# ltc4063-test.net
KiCad netlist of a schematic drawn in EAGLE
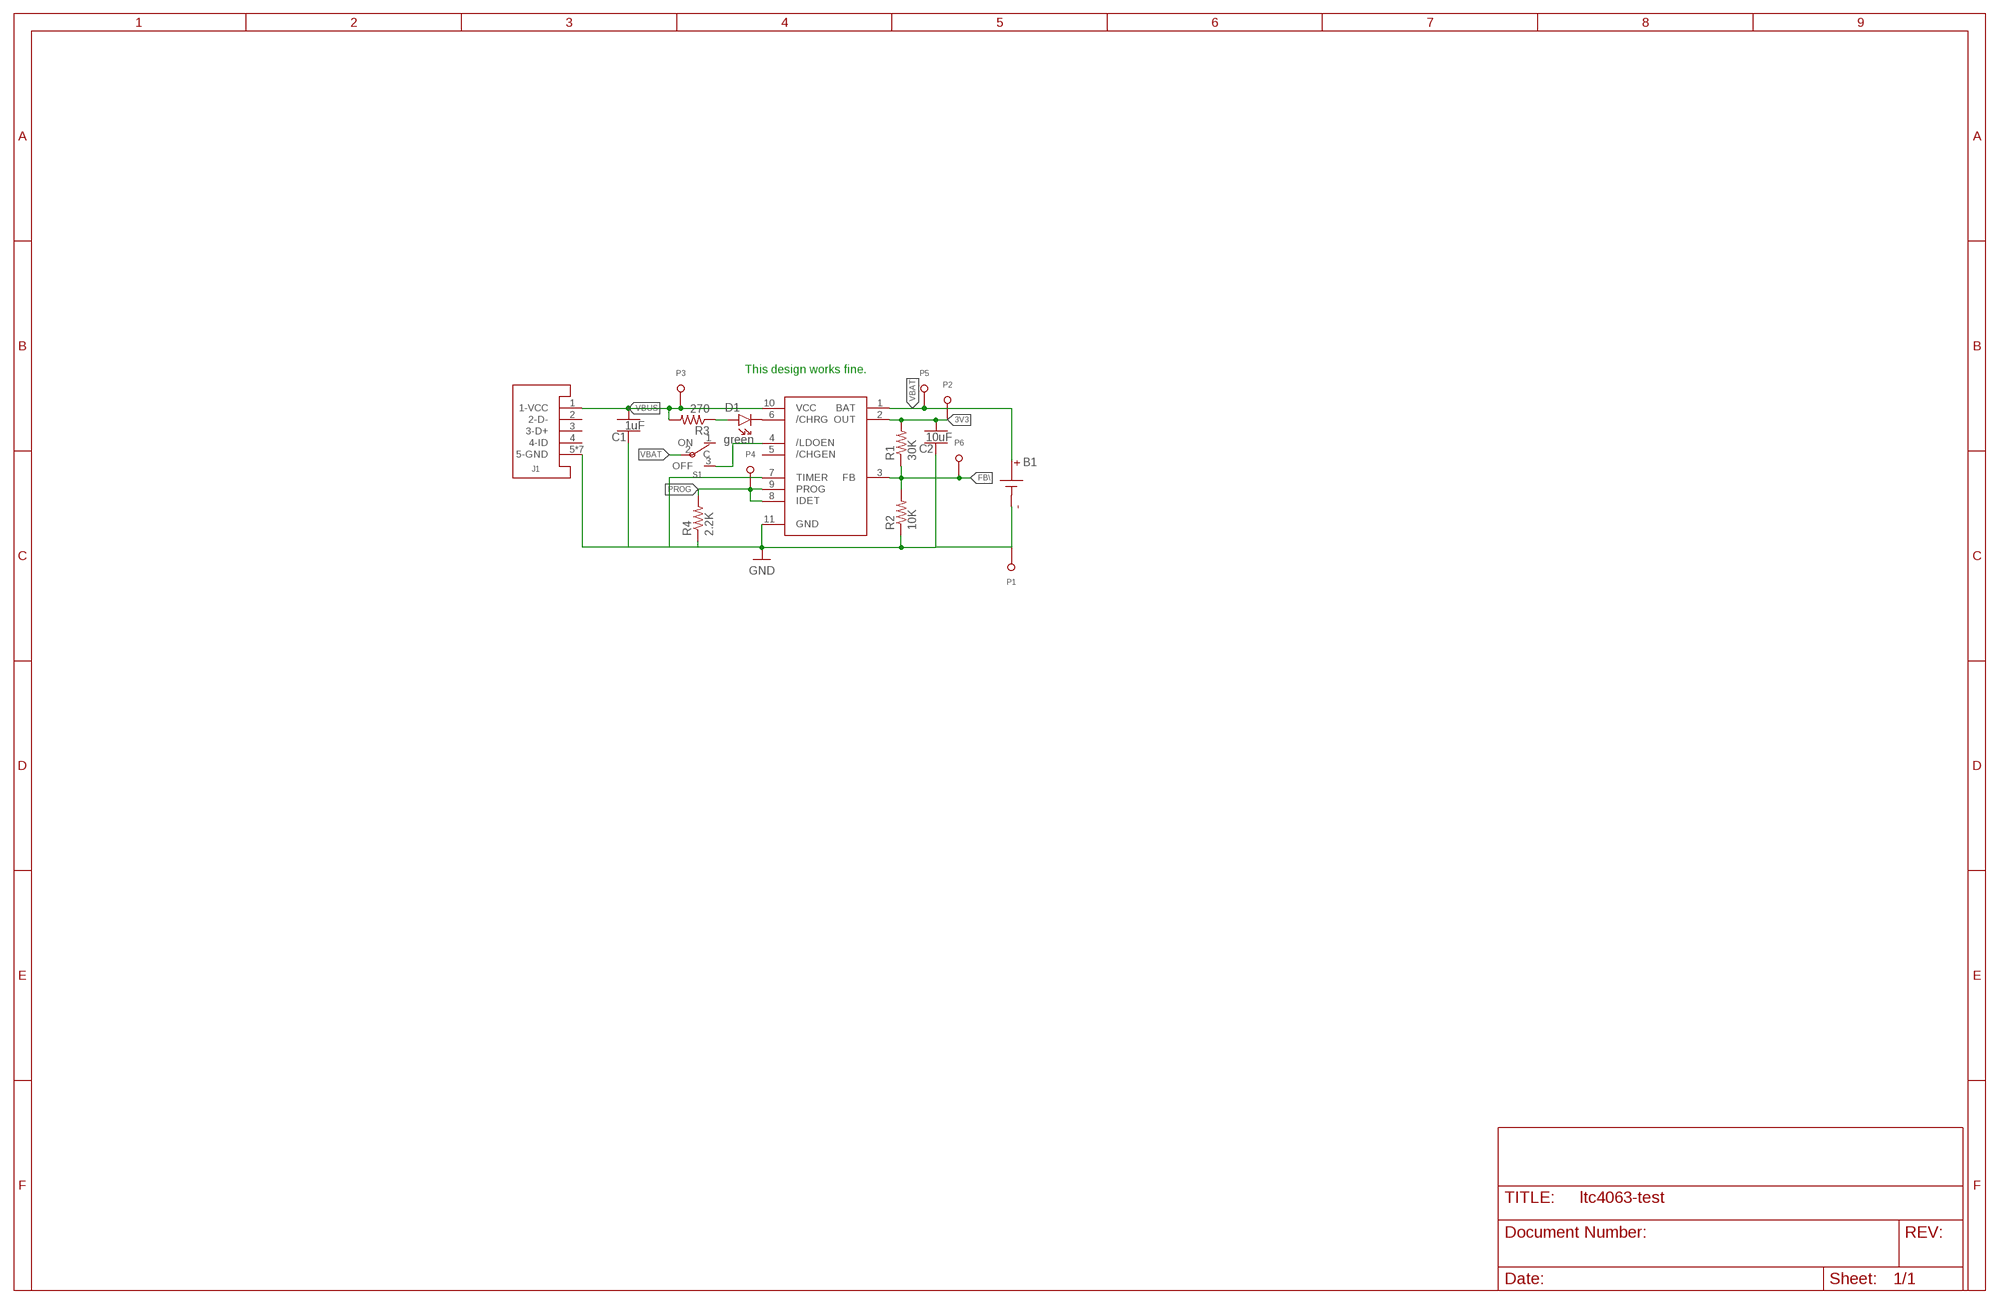
[diagram p0: schematic, sheet 1]

(export (version "E")
  (design (tool "Eeschema 10.0.6"))
  (components
    (comp (ref "B1")
      (value "BATTERY-SPRING-SMD")
      (footprint "eagle-import:WIRE-TERMINAL-1X2-2.5MM-SMD-AVX-009276002021106")
      (fields (field (name "CREATOR") "Swanson"))
      (libsource (lib "eagle-import") (part "BATTERY-SPRING-SMD"))
    )
    (comp (ref "C1")
      (value "1uF")
      (footprint "eagle-import:CAPC2012X140_HS")
      (fields
        (field (name "MFR") "Taiyo Yuden")
        (field (name "MPN") "TMK212B7105KG-T")
        (field (name "CREATOR") "Swanson")
        (field (name "REVIEWER") "Swanson")
      )
      (libsource (lib "eagle-import") (part "CAPACITOR-NP_SMD-2012-0805_CERAMIC-1UF"))
    )
    (comp (ref "C2")
      (value "10uF")
      (footprint "eagle-import:CAPC2012X140_HS")
      (fields (field (name "CREATOR") "Swanson") (field (name "REVIEWER") "Swanson"))
      (libsource (lib "eagle-import") (part "CAPACITOR-NP_SMD-2012-0805_CERAMIC-10UF"))
    )
    (comp (ref "D1")
      (value "green")
      (footprint "eagle-import:LEDSC125X200X120-2_HS")
      (fields
        (field (name "MFR") "Lite-On Inc")
        (field (name "MPN") "LTST-C170GKT")
        (field (name "CREATOR") "Swanson")
        (field (name "REVIEWER") "Swanson")
      )
      (libsource (lib "eagle-import") (part "DIODE-LED_SMD-2012-0805-GREEN"))
    )
    (comp (ref "J1")
      (value "USB-MICROA-AMPHENOL-10118192-0001LF")
      (footprint "eagle-import:USB-MICROA-10118192-0001LF")
      (fields (field (name "CREATOR") "Swanson"))
      (libsource (lib "eagle-import") (part "USB-MICROA-AMPHENOL-10118192-0001LF"))
    )
    (comp (ref "P1")
      (value "TEST-POINT")
      (footprint "eagle-import:TEST-POINT-KEYSTONE-5000")
      (fields (field (name "CREATOR") "Swanson"))
      (libsource (lib "eagle-import") (part "TEST-POINT"))
    )
    (comp (ref "P2")
      (value "TEST-POINT")
      (footprint "eagle-import:TEST-POINT-KEYSTONE-5000")
      (fields (field (name "CREATOR") "Swanson"))
      (libsource (lib "eagle-import") (part "TEST-POINT"))
    )
    (comp (ref "P3")
      (value "TEST-POINT")
      (footprint "eagle-import:TEST-POINT-KEYSTONE-5000")
      (fields (field (name "CREATOR") "Swanson"))
      (libsource (lib "eagle-import") (part "TEST-POINT"))
    )
    (comp (ref "P4")
      (value "TEST-POINT")
      (footprint "eagle-import:TEST-POINT-KEYSTONE-5000")
      (fields (field (name "CREATOR") "Swanson"))
      (libsource (lib "eagle-import") (part "TEST-POINT"))
    )
    (comp (ref "P5")
      (value "TEST-POINT")
      (footprint "eagle-import:TEST-POINT-KEYSTONE-5000")
      (fields (field (name "CREATOR") "Swanson"))
      (libsource (lib "eagle-import") (part "TEST-POINT"))
    )
    (comp (ref "P6")
      (value "TEST-POINT")
      (footprint "eagle-import:TEST-POINT-KEYSTONE-5000")
      (fields (field (name "CREATOR") "Swanson"))
      (libsource (lib "eagle-import") (part "TEST-POINT"))
    )
    (comp (ref "R1")
      (value "30K")
      (footprint "eagle-import:RESC2012X60_HS")
      (fields (field (name "CREATOR") "Swanson"))
      (libsource (lib "eagle-import") (part "RESISTOR_SMD-2012-0805-30K"))
    )
    (comp (ref "R2")
      (value "10K")
      (footprint "eagle-import:RESC2012X60_HS")
      (fields
        (field (name "MFR") "Yageo")
        (field (name "MPN") "RC0805JR-0710KL")
        (field (name "CREATOR") "Swanson")
        (field (name "REVIEWER") "Swanson")
      )
      (libsource (lib "eagle-import") (part "RESISTOR_SMD-2012-0805-10K"))
    )
    (comp (ref "R3")
      (value "270")
      (footprint "eagle-import:RESC2012X60_HS")
      (fields (field (name "CREATOR") "SWANSON"))
      (libsource (lib "eagle-import") (part "RESISTOR_SMD-2012-0805-270"))
    )
    (comp (ref "R4")
      (value "2.2K")
      (footprint "eagle-import:RESC2012X60_HS")
      (fields (field (name "CREATOR") "SWANSON"))
      (libsource (lib "eagle-import") (part "RESISTOR_SMD-2012-0805-2.2K"))
    )
    (comp (ref "S1")
      (value "POWER-SWITCH-MFS201N-9-Z-SMD-VERTICAL")
      (footprint "eagle-import:JS102011JCQN")
      (fields (field (name "CREATOR") "Swanson"))
      (libsource (lib "eagle-import") (part "POWER-SWITCH-MFS201N-9-Z-SMD-VERTICAL"))
    )
    (comp (ref "U1")
      (value "LIPO-VREG-LTC4063")
      (footprint "eagle-import:SON50P300X300X80-11T165X238")
      (fields (field (name "CREATOR") "Swanson"))
      (libsource (lib "eagle-import") (part "LIPO-VREG-LTC4063"))
    )
  )
  (nets
    (net (code "1") (name "3V3") (class "Default")
      (node (ref "C2") (pin "2") (pinfunction "2_2") (pintype "passive"))
      (node (ref "P2") (pin "T") (pinfunction "T_T") (pintype "bidirectional"))
      (node (ref "R1") (pin "2") (pinfunction "2_2") (pintype "passive"))
      (node (ref "U1") (pin "2") (pinfunction "OUT_2") (pintype "bidirectional"))
    )
    (net (code "2") (name "FB\\") (class "Default")
      (node (ref "P6") (pin "T") (pinfunction "T_T") (pintype "bidirectional"))
      (node (ref "R1") (pin "1") (pinfunction "1_1") (pintype "passive"))
      (node (ref "R2") (pin "2") (pinfunction "2_2") (pintype "passive"))
      (node (ref "U1") (pin "3") (pinfunction "FB_3") (pintype "bidirectional"))
    )
    (net (code "3") (name "GND") (class "Default")
      (node (ref "B1") (pin "2A") (pinfunction "N_2A") (pintype "bidirectional"))
      (node (ref "B1") (pin "2B") (pinfunction "N_2B") (pintype "bidirectional"))
      (node (ref "C1") (pin "1") (pinfunction "1_1") (pintype "passive"))
      (node (ref "C2") (pin "1") (pinfunction "1_1") (pintype "passive"))
      (node (ref "J1") (pin "10") (pinfunction "5-GND_10") (pintype "bidirectional"))
      (node (ref "J1") (pin "11") (pinfunction "5-GND_11") (pintype "bidirectional"))
      (node (ref "J1") (pin "5") (pinfunction "5-GND_5") (pintype "bidirectional"))
      (node (ref "J1") (pin "6") (pinfunction "5-GND_6") (pintype "bidirectional"))
      (node (ref "J1") (pin "7") (pinfunction "5-GND_7") (pintype "bidirectional"))
      (node (ref "J1") (pin "8") (pinfunction "5-GND_8") (pintype "bidirectional"))
      (node (ref "J1") (pin "9") (pinfunction "5-GND_9") (pintype "bidirectional"))
      (node (ref "P1") (pin "T") (pinfunction "T_T") (pintype "bidirectional"))
      (node (ref "R2") (pin "1") (pinfunction "1_1") (pintype "passive"))
      (node (ref "R4") (pin "1") (pinfunction "1_1") (pintype "passive"))
      (node (ref "U1") (pin "11") (pinfunction "GND_11") (pintype "bidirectional"))
      (node (ref "U1") (pin "7") (pinfunction "TIMER_7") (pintype "bidirectional"))
    )
    (net (code "4") (name "Net-(D1-PadA)") (class "Default")
      (node (ref "D1") (pin "A") (pinfunction "A_A") (pintype "passive"))
      (node (ref "R3") (pin "1") (pinfunction "1_1") (pintype "passive"))
    )
    (net (code "5") (name "Net-(S1-OFF)") (class "Default")
      (node (ref "S1") (pin "3") (pinfunction "OFF_3") (pintype "bidirectional"))
      (node (ref "U1") (pin "4") (pinfunction "/LDOEN_4") (pintype "bidirectional"))
    )
    (net (code "6") (name "Net-(U1-{slash}CHRG)") (class "Default")
      (node (ref "D1") (pin "C") (pinfunction "C_C") (pintype "passive"))
      (node (ref "U1") (pin "6") (pinfunction "/CHRG_6") (pintype "bidirectional"))
    )
    (net (code "7") (name "PROG") (class "Default")
      (node (ref "P4") (pin "T") (pinfunction "T_T") (pintype "bidirectional"))
      (node (ref "R4") (pin "2") (pinfunction "2_2") (pintype "passive"))
      (node (ref "U1") (pin "8") (pinfunction "IDET_8") (pintype "bidirectional"))
      (node (ref "U1") (pin "9") (pinfunction "PROG_9") (pintype "bidirectional"))
    )
    (net (code "8") (name "VBAT") (class "Default")
      (node (ref "B1") (pin "1A") (pinfunction "P_1A") (pintype "bidirectional"))
      (node (ref "B1") (pin "1B") (pinfunction "P_1B") (pintype "bidirectional"))
      (node (ref "P5") (pin "T") (pinfunction "T_T") (pintype "bidirectional"))
      (node (ref "S1") (pin "2") (pinfunction "C_2") (pintype "bidirectional"))
      (node (ref "U1") (pin "1") (pinfunction "BAT_1") (pintype "bidirectional"))
    )
    (net (code "9") (name "VBUS") (class "Default")
      (node (ref "C1") (pin "2") (pinfunction "2_2") (pintype "passive"))
      (node (ref "J1") (pin "1") (pinfunction "1-VCC_1") (pintype "bidirectional"))
      (node (ref "P3") (pin "T") (pinfunction "T_T") (pintype "bidirectional"))
      (node (ref "R3") (pin "2") (pinfunction "2_2") (pintype "passive"))
      (node (ref "U1") (pin "10") (pinfunction "VCC_10") (pintype "bidirectional"))
    )
    (net (code "10") (name "unconnected-(J1-2-D--Pad2)") (class "Default")
      (node (ref "J1") (pin "2") (pinfunction "2-D-_2") (pintype "bidirectional"))
    )
    (net (code "11") (name "unconnected-(J1-3-D+-Pad3)") (class "Default")
      (node (ref "J1") (pin "3") (pinfunction "3-D+_3") (pintype "bidirectional"))
    )
    (net (code "12") (name "unconnected-(J1-4-ID-Pad4)") (class "Default")
      (node (ref "J1") (pin "4") (pinfunction "4-ID_4") (pintype "bidirectional"))
    )
    (net (code "13") (name "unconnected-(S1-ON-Pad1)") (class "Default")
      (node (ref "S1") (pin "1") (pinfunction "ON_1") (pintype "bidirectional"))
    )
    (net (code "14") (name "unconnected-(U1-{slash}CHGEN-Pad5)") (class "Default")
      (node (ref "U1") (pin "5") (pinfunction "/CHGEN_5") (pintype "bidirectional"))
    )
  )
)
